# Voltage_Sensor.net
KiCad netlist of a schematic drawn in Altium Designer
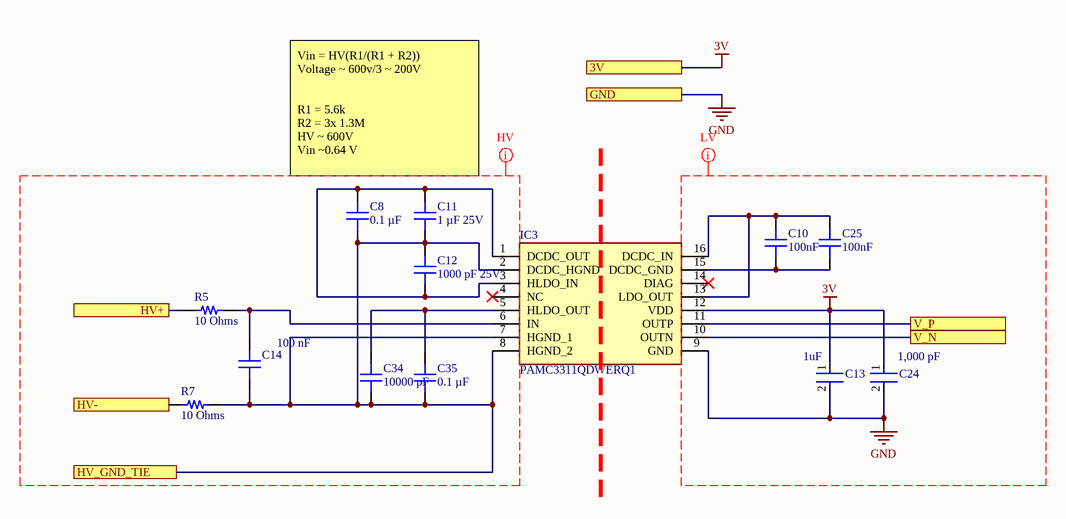
[diagram p0: Voltage Sensor.SchDoc]

(export (version "E")
  (design (tool "Eeschema 10.0.6"))
  (components
    (comp (ref "C8")
      (value "0.1 µF")
      (footprint "CAP 0402_1005")
      (description "CAP CER 0402 0.1UF 16V X7R 10%")
      (fields
        (field (name "PART NUMBER") "C0402C104K4RECAUTO")
        (field (name "CAPACITANCE") "0.1 µF")
        (field (name "MANUFACTURER") "KEMET")
      )
      (libsource (lib "Celestial Altium Library - altium_library") (part "Capacitor"))
    )
    (comp (ref "C10")
      (value "100nF")
      (footprint "CAP 0402_1005")
      (description "CAP CER 2.2UF 25V X5R 0402")
      (fields
        (field (name "PART NUMBER") "ZRB157R61E225KE11D")
        (field (name "MANUFACTURER") "Murata Electronics")
      )
      (libsource (lib "Celestial Altium Library - altium_library") (part "Capacitor"))
    )
    (comp (ref "C11")
      (value "1 µF")
      (footprint "MURATA GRM155 0402_1005")
      (description "CAP CER 1UF 10V X7S 0402")
      (fields
        (field (name "PART NUMBER") "GRM155C71A105KE11D")
        (field (name "CAPACITANCE") "1 µF 25V")
        (field (name "MANUFACTURER") "Murata Electronics")
      )
      (libsource (lib "Celestial Altium Library - altium_library") (part "Capacitor"))
    )
    (comp (ref "C12")
      (value "1000 pF")
      (footprint "CAP 0402_1005")
      (description "CAP CER 1000PF 50V C0G/NP0 0402")
      (fields
        (field (name "PART NUMBER") "UMK105CG102JVHF")
        (field (name "CAPACITANCE") "1000 pF 25V")
        (field (name "MANUFACTURER") "Taiyo Yuden")
      )
      (libsource (lib "Celestial Altium Library - altium_library") (part "Capacitor"))
    )
    (comp (ref "C13")
      (value "CGA3E1X7R1E105K080AC")
      (footprint "FP-CGA3E-0_3-0_1-IPC_A")
      (description "Cap Ceramic 1uF 25V X7R 10% Pad SMD 0603 +125°C Automotive T/R")
      (fields
        (field (name "CAPACITANCE") "1uF")
        (field (name "VOLTAGE") "25V")
        (field (name "TOLERANCE") "10%")
      )
      (libsource (lib "Altium Content Vault") (part "b4654b650e69147ec39a6b967a45e02"))
    )
    (comp (ref "C14")
      (value "100 nF")
      (footprint "CAP 0603_1608")
      (fields
        (field (name "PART NUMBER") "VJ0603Y104MXQCW1BC")
        (field (name "MANUFACTURER") "Vishay Vitramon")
        (field (name "TOLERANCE") "±20%")
      )
      (libsource (lib "Celestial Altium Library - altium_library") (part "Capacitor"))
    )
    (comp (ref "C24")
      (value "C0603C102K5RACTU")
      (footprint "FP-C0603C-CF-MFG")
      (description "CAP CER 1000PF 50V X7R 0603")
      (fields
        (field (name "TOLERANCE") "0.1")
        (field (name "CAPACITANCE") "1,000 pF")
        (field (name "OCTOPART") "https://octopart.com/c0603c102k5ractu-kemet-144878")
      )
      (libsource (lib "Altium Content Vault") (part "b4654b650e69147ec39a6b967a45e02"))
    )
    (comp (ref "C25")
      (value "100nF")
      (footprint "CAP 0402_1005")
      (description "CAP CER 2.2UF 25V X5R 0402")
      (fields
        (field (name "PART NUMBER") "ZRB157R61E225KE11D")
        (field (name "MANUFACTURER") "Murata Electronics")
      )
      (libsource (lib "Celestial Altium Library - altium_library") (part "Capacitor"))
    )
    (comp (ref "C34")
      (value "10000 pF")
      (footprint "CAP 0402_1005")
      (description "CAP CER 10000PF 25V X5R 0402")
      (fields
        (field (name "PART NUMBER") "TMK105BJ103KP-F")
        (field (name "CAPACITANCE") "10000 pF")
        (field (name "MANUFACTURER") "Taiyo Yuden")
      )
      (libsource (lib "Celestial Altium Library - altium_library") (part "Capacitor"))
    )
    (comp (ref "C35")
      (value "0.1 µF")
      (footprint "CAP 0402_1005")
      (description "CAP CER 0402 0.1UF 16V X7R 10%")
      (fields
        (field (name "PART NUMBER") "C0402C104K4RECAUTO")
        (field (name "CAPACITANCE") "0.1 µF")
        (field (name "MANUFACTURER") "KEMET")
      )
      (libsource (lib "Celestial Altium Library - altium_library") (part "Capacitor"))
    )
    (comp (ref "IC3")
      (value "PAMC3311QDWERQ1")
      (footprint "SamacSys:SOIC127P1030X265-16N")
      (description "Integrated Circuit")
      (libsource (lib "*") (part "PAMC3311QDWERQ1"))
    )
    (comp (ref "R5")
      (value "10 Ohms")
      (footprint "RES 0402_1005")
      (description "RES 10 OHM 5% 1/16W 0402")
      (fields
        (field (name "PART NUMBER") "WR04X100 JTL")
        (field (name "MANUFACTURER") "Walsin Technology Corporation")
      )
      (libsource (lib "Celestial Altium Library - altium_library") (part "Resistor"))
    )
    (comp (ref "R7")
      (value "10 Ohms")
      (footprint "RES 0402_1005")
      (description "RES 10 OHM 5% 1/16W 0402")
      (fields
        (field (name "PART NUMBER") "WR04X100 JTL")
        (field (name "MANUFACTURER") "Walsin Technology Corporation")
      )
      (libsource (lib "Celestial Altium Library - altium_library") (part "Resistor"))
    )
  )
  (nets
    (net (code "1") (name "/HV+") (class "Default")
      (node (ref "R5") (pin "1") (pinfunction "1_1") (pintype "passive"))
    )
    (net (code "2") (name "/HV-") (class "Default")
      (node (ref "R7") (pin "1") (pinfunction "1_1") (pintype "passive"))
    )
    (net (code "3") (name "/HV_GND_TIE") (class "Default")
      (node (ref "C11") (pin "1") (pinfunction "1_1") (pintype "passive"))
      (node (ref "C12") (pin "2") (pinfunction "2_2") (pintype "passive"))
      (node (ref "C14") (pin "1") (pinfunction "1_1") (pintype "passive"))
      (node (ref "C34") (pin "1") (pinfunction "1_1") (pintype "passive"))
      (node (ref "C35") (pin "1") (pinfunction "1_1") (pintype "passive"))
      (node (ref "C8") (pin "1") (pinfunction "1_1") (pintype "passive"))
      (node (ref "IC3") (pin "2") (pinfunction "DCDC_HGND_2") (pintype "passive"))
      (node (ref "IC3") (pin "7") (pinfunction "HGND_1_7") (pintype "passive"))
      (node (ref "IC3") (pin "8") (pinfunction "HGND_2_8") (pintype "passive"))
      (node (ref "R7") (pin "2") (pinfunction "2_2") (pintype "passive"))
    )
    (net (code "4") (name "/V_N") (class "Default")
      (node (ref "IC3") (pin "10") (pinfunction "OUTN_10") (pintype "passive"))
    )
    (net (code "5") (name "/V_P") (class "Default")
      (node (ref "IC3") (pin "11") (pinfunction "OUTP_11") (pintype "passive"))
    )
    (net (code "6") (name "3V") (class "Default")
      (node (ref "C13") (pin "1") (pinfunction "1_1") (pintype "passive"))
      (node (ref "C24") (pin "1") (pinfunction "1_1") (pintype "passive"))
      (node (ref "IC3") (pin "12") (pinfunction "VDD_12") (pintype "passive"))
    )
    (net (code "7") (name "GND") (class "Default")
      (node (ref "C13") (pin "2") (pinfunction "2_2") (pintype "passive"))
      (node (ref "C24") (pin "2") (pinfunction "2_2") (pintype "passive"))
      (node (ref "IC3") (pin "9") (pinfunction "GND_9") (pintype "passive"))
    )
    (net (code "8") (name "Net-(IC3-DCDC_GND)") (class "Default")
      (node (ref "C10") (pin "1") (pinfunction "1_1") (pintype "passive"))
      (node (ref "C25") (pin "1") (pinfunction "1_1") (pintype "passive"))
      (node (ref "IC3") (pin "15") (pinfunction "DCDC_GND_15") (pintype "passive"))
    )
    (net (code "9") (name "Net-(IC3-DCDC_IN)") (class "Default")
      (node (ref "C10") (pin "2") (pinfunction "2_2") (pintype "passive"))
      (node (ref "C25") (pin "2") (pinfunction "2_2") (pintype "passive"))
      (node (ref "IC3") (pin "13") (pinfunction "LDO_OUT_13") (pintype "passive"))
      (node (ref "IC3") (pin "16") (pinfunction "DCDC_IN_16") (pintype "passive"))
    )
    (net (code "10") (name "Net-(IC3-DCDC_OUT)") (class "Default")
      (node (ref "C11") (pin "2") (pinfunction "2_2") (pintype "passive"))
      (node (ref "C12") (pin "1") (pinfunction "1_1") (pintype "passive"))
      (node (ref "C8") (pin "2") (pinfunction "2_2") (pintype "passive"))
      (node (ref "IC3") (pin "1") (pinfunction "DCDC_OUT_1") (pintype "passive"))
      (node (ref "IC3") (pin "3") (pinfunction "HLDO_IN_3") (pintype "passive"))
    )
    (net (code "11") (name "Net-(IC3-HLDO_OUT)") (class "Default")
      (node (ref "C34") (pin "2") (pinfunction "2_2") (pintype "passive"))
      (node (ref "C35") (pin "2") (pinfunction "2_2") (pintype "passive"))
      (node (ref "IC3") (pin "5") (pinfunction "HLDO_OUT_5") (pintype "passive"))
    )
    (net (code "12") (name "Net-(IC3-IN)") (class "Default")
      (node (ref "C14") (pin "2") (pinfunction "2_2") (pintype "passive"))
      (node (ref "IC3") (pin "6") (pinfunction "IN_6") (pintype "passive"))
      (node (ref "R5") (pin "2") (pinfunction "2_2") (pintype "passive"))
    )
    (net (code "13") (name "unconnected-(IC3-DIAG-Pad14)") (class "Default")
      (node (ref "IC3") (pin "14") (pinfunction "DIAG_14") (pintype "passive+no_connect"))
    )
    (net (code "14") (name "unconnected-(IC3-NC-Pad4)") (class "Default")
      (node (ref "IC3") (pin "4") (pinfunction "NC_4") (pintype "passive+no_connect"))
    )
  )
)
